# Accumulator_Voltage_Indicator.net
KiCad netlist of a schematic drawn in Altium Designer
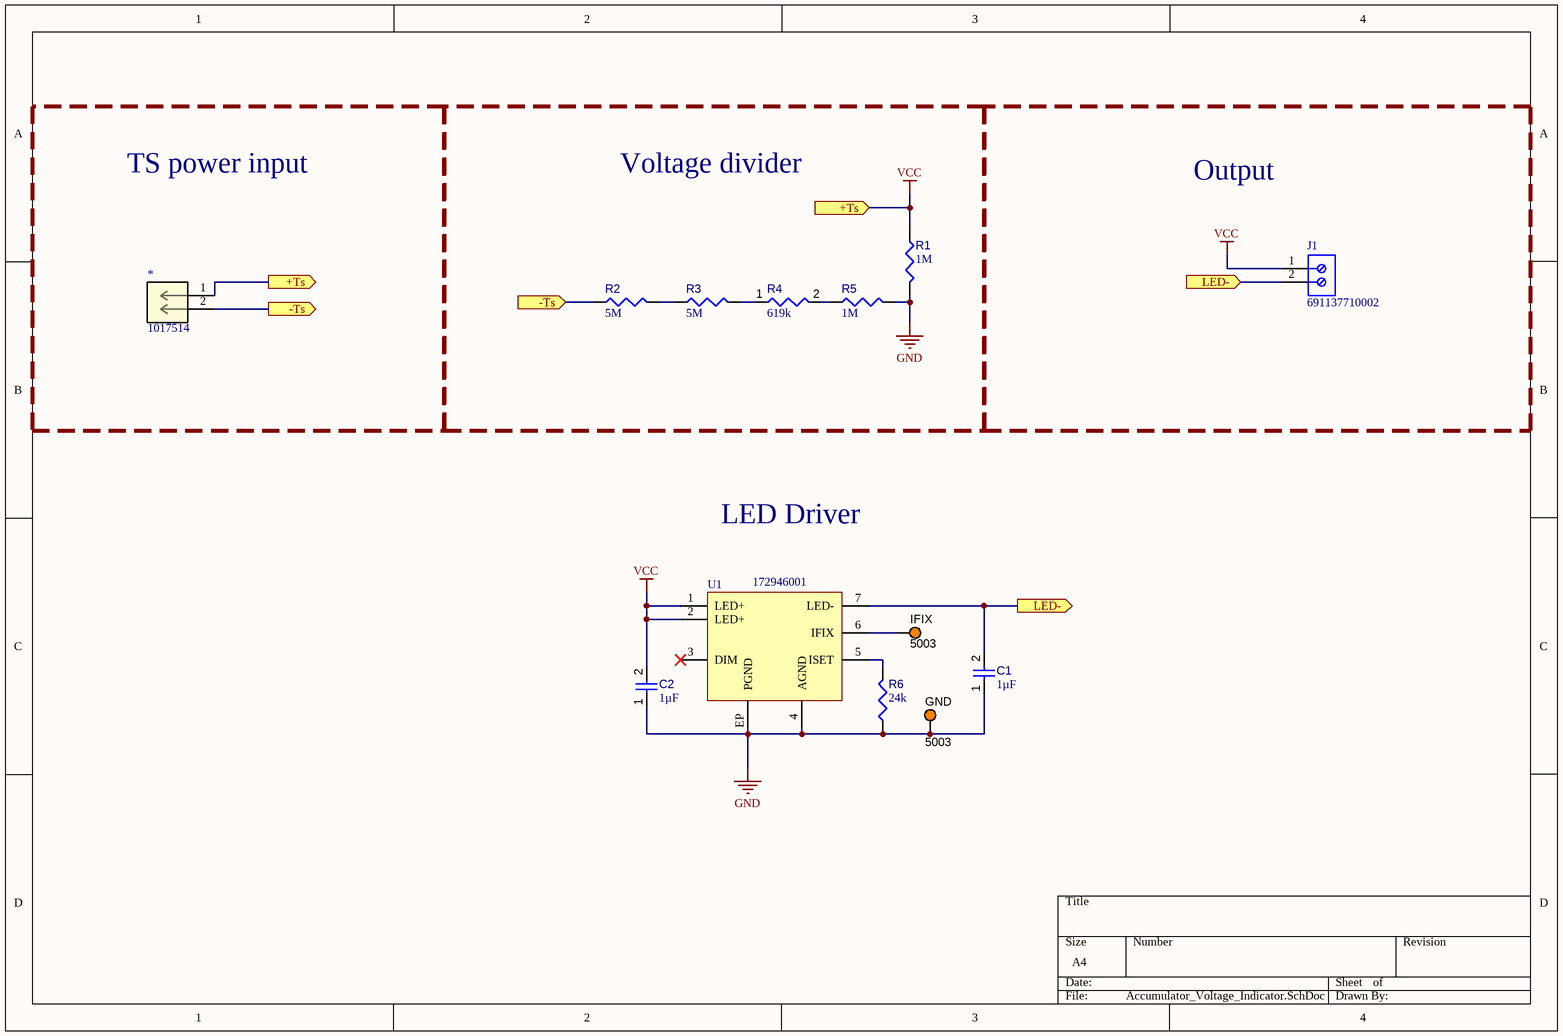
[diagram p0: Accumulator_Voltage_Indicator.SchDoc]

(export (version "E")
  (design (tool "Eeschema 10.0.6"))
  (components
    (comp (ref "*")
      (value "1017514")
      (footprint "CONN_1017514")
      (description "Barrier Strip Terminal Block")
      (libsource (lib "UWindsor Formula Electric") (part "1017514-Symbol-1"))
    )
    (comp (ref "C1")
      (value "1µF")
      (footprint "CAPC0603(1608)100_L")
      (description "Chip Capacitor, 1µF +/-0.1%, 25V, 0603, Thickness 1 mm")
      (fields (field (name "TOLERANCE") "20%") (field (name "Comment") "Capacitor 1µF +/-0.1% 25V 0603"))
      (libsource (lib "UWindsor Formula Electric") (part "CAP-NP-2"))
    )
    (comp (ref "C2")
      (value "1µF")
      (footprint "CAPC0603(1608)100_L")
      (description "Chip Capacitor, 1µF +/-0.1%, 25V, 0603, Thickness 1 mm")
      (fields (field (name "TOLERANCE") "20%") (field (name "Comment") "Capacitor 1µF +/-0.1% 25V 0603"))
      (libsource (lib "UWindsor Formula Electric") (part "CAP-NP-2"))
    )
    (comp (ref "GND")
      (value "5003")
      (footprint "KSTN-5003")
      (description "Test Point, Orange, Height 4.6 mm, Tail Length 3 mm, 1-Pin THD, RoHS")
      (fields (field (name "MANUFACTURER") "Keystone"))
      (libsource (lib "UWindsor Formula Electric") (part "TESTPOINT_ORANGE"))
    )
    (comp (ref "IFIX")
      (value "5003")
      (footprint "KSTN-5003")
      (description "Test Point, Orange, Height 4.6 mm, Tail Length 3 mm, 1-Pin THD, RoHS")
      (fields (field (name "MANUFACTURER") "Keystone"))
      (libsource (lib "UWindsor Formula Electric") (part "TESTPOINT_ORANGE"))
    )
    (comp (ref "J1")
      (value "691137710002")
      (footprint "691137710002")
      (description "Series 1377 - 5.00 mm Horizontal Entry with Pressure Clamp WR-TBL, 2 pin")
      (libsource (lib "UWindsor Formula Electric") (part "TBL - 1R - 02P - Screw"))
    )
    (comp (ref "R1")
      (value "1M")
      (footprint "RESC5025X65N")
      (fields
        (field (name "TOLERANCE") "1%")
        (field (name "POWER") "750mW")
        (field (name "Comment") "RMCF2010FT1M00")
      )
      (libsource (lib "UWindsor Formula Electric") (part "RES-2"))
    )
    (comp (ref "R2")
      (value "5M")
      (footprint "RES_2512_OHM-L")
      (fields
        (field (name "POWER") "1W")
        (field (name "TOLERANCE") "5%")
        (field (name "Comment") "HVC2512T5004JET")
      )
      (libsource (lib "UWindsor Formula Electric") (part "RES-2"))
    )
    (comp (ref "R3")
      (value "5M")
      (footprint "RES_2512_OHM-L")
      (fields
        (field (name "POWER") "1W")
        (field (name "TOLERANCE") "5%")
        (field (name "Comment") "HVC2512T5004JET")
      )
      (libsource (lib "UWindsor Formula Electric") (part "RES-2"))
    )
    (comp (ref "R4")
      (value "619k")
      (footprint "RESC5025X65N")
      (description "RES SMD 619K OHM 1% 3/4W 2010")
      (fields (field (name "MP") "RC2010FK-07619KL"))
      (libsource (lib "UWindsor Formula Electric") (part "121KR2F"))
    )
    (comp (ref "R5")
      (value "1M")
      (footprint "RESC5025X65N")
      (fields
        (field (name "TOLERANCE") "1%")
        (field (name "POWER") "750mW")
        (field (name "Comment") "RMCF2010FT1M00")
      )
      (libsource (lib "UWindsor Formula Electric") (part "RES-2"))
    )
    (comp (ref "R6")
      (value "24k")
      (footprint "RESC0603(1608)_L")
      (fields
        (field (name "TOLERANCE") "5%")
        (field (name "POWER") "100mW")
        (field (name "Comment") "RC0603JR-0724KL")
      )
      (libsource (lib "UWindsor Formula Electric") (part "RES-2"))
    )
    (comp (ref "U1")
      (value "172946001")
      (footprint "WPME-LDHM_TO263-7EP_L13.77W10.16H4.57")
      (description "LED Driver, 16-Segment")
      (libsource (lib "UWindsor Formula Electric") (part "TO263-7EP_WPME-LDHM"))
    )
  )
  (nets
    (net (code "1") (name "/-Ts") (class "Default")
      (node (ref "*") (pin "2") (pinfunction "2_2") (pintype "passive"))
      (node (ref "R2") (pin "1") (pinfunction "1_1") (pintype "passive"))
    )
    (net (code "2") (name "/LED-") (class "Default")
      (node (ref "C1") (pin "2") (pinfunction "2_2") (pintype "passive"))
      (node (ref "J1") (pin "2") (pinfunction "2_2") (pintype "passive"))
      (node (ref "U1") (pin "7") (pinfunction "LED-_7") (pintype "passive"))
    )
    (net (code "3") (name "GND") (class "Default")
      (node (ref "C1") (pin "1") (pinfunction "1_1") (pintype "passive"))
      (node (ref "C2") (pin "1") (pinfunction "1_1") (pintype "passive"))
      (node (ref "GND") (pin "1") (pinfunction "1_1") (pintype "passive"))
      (node (ref "R1") (pin "2") (pinfunction "2_2") (pintype "passive"))
      (node (ref "R5") (pin "2") (pinfunction "2_2") (pintype "passive"))
      (node (ref "R6") (pin "1") (pinfunction "1_1") (pintype "passive"))
      (node (ref "U1") (pin "4") (pinfunction "AGND_4") (pintype "passive"))
      (node (ref "U1") (pin "EP") (pinfunction "PGND_EP") (pintype "passive"))
    )
    (net (code "4") (name "Net-(R2-Pad2)") (class "Default")
      (node (ref "R2") (pin "2") (pinfunction "2_2") (pintype "passive"))
      (node (ref "R3") (pin "1") (pinfunction "1_1") (pintype "passive"))
    )
    (net (code "5") (name "Net-(R3-Pad2)") (class "Default")
      (node (ref "R3") (pin "2") (pinfunction "2_2") (pintype "passive"))
      (node (ref "R4") (pin "1") (pinfunction "1_1") (pintype "passive"))
    )
    (net (code "6") (name "Net-(R4-Pad2)") (class "Default")
      (node (ref "R4") (pin "2") (pinfunction "2_2") (pintype "passive"))
      (node (ref "R5") (pin "1") (pinfunction "1_1") (pintype "passive"))
    )
    (net (code "7") (name "Net-(U1-IFIX)") (class "Default")
      (node (ref "IFIX") (pin "1") (pinfunction "1_1") (pintype "passive"))
      (node (ref "U1") (pin "6") (pinfunction "IFIX_6") (pintype "passive"))
    )
    (net (code "8") (name "Net-(U1-ISET)") (class "Default")
      (node (ref "R6") (pin "2") (pinfunction "2_2") (pintype "passive"))
      (node (ref "U1") (pin "5") (pinfunction "ISET_5") (pintype "passive"))
    )
    (net (code "9") (name "VCC") (class "Default")
      (node (ref "*") (pin "1") (pinfunction "1_1") (pintype "passive"))
      (node (ref "C2") (pin "2") (pinfunction "2_2") (pintype "passive"))
      (node (ref "J1") (pin "1") (pinfunction "1_1") (pintype "passive"))
      (node (ref "R1") (pin "1") (pinfunction "1_1") (pintype "passive"))
      (node (ref "U1") (pin "1") (pinfunction "LED+_1") (pintype "passive"))
      (node (ref "U1") (pin "2") (pinfunction "LED+_2") (pintype "passive"))
    )
    (net (code "10") (name "unconnected-(U1-DIM-Pad3)") (class "Default")
      (node (ref "U1") (pin "3") (pinfunction "DIM_3") (pintype "passive+no_connect"))
    )
  )
)
